# PSU.net
KiCad netlist of a schematic drawn in Altium Designer
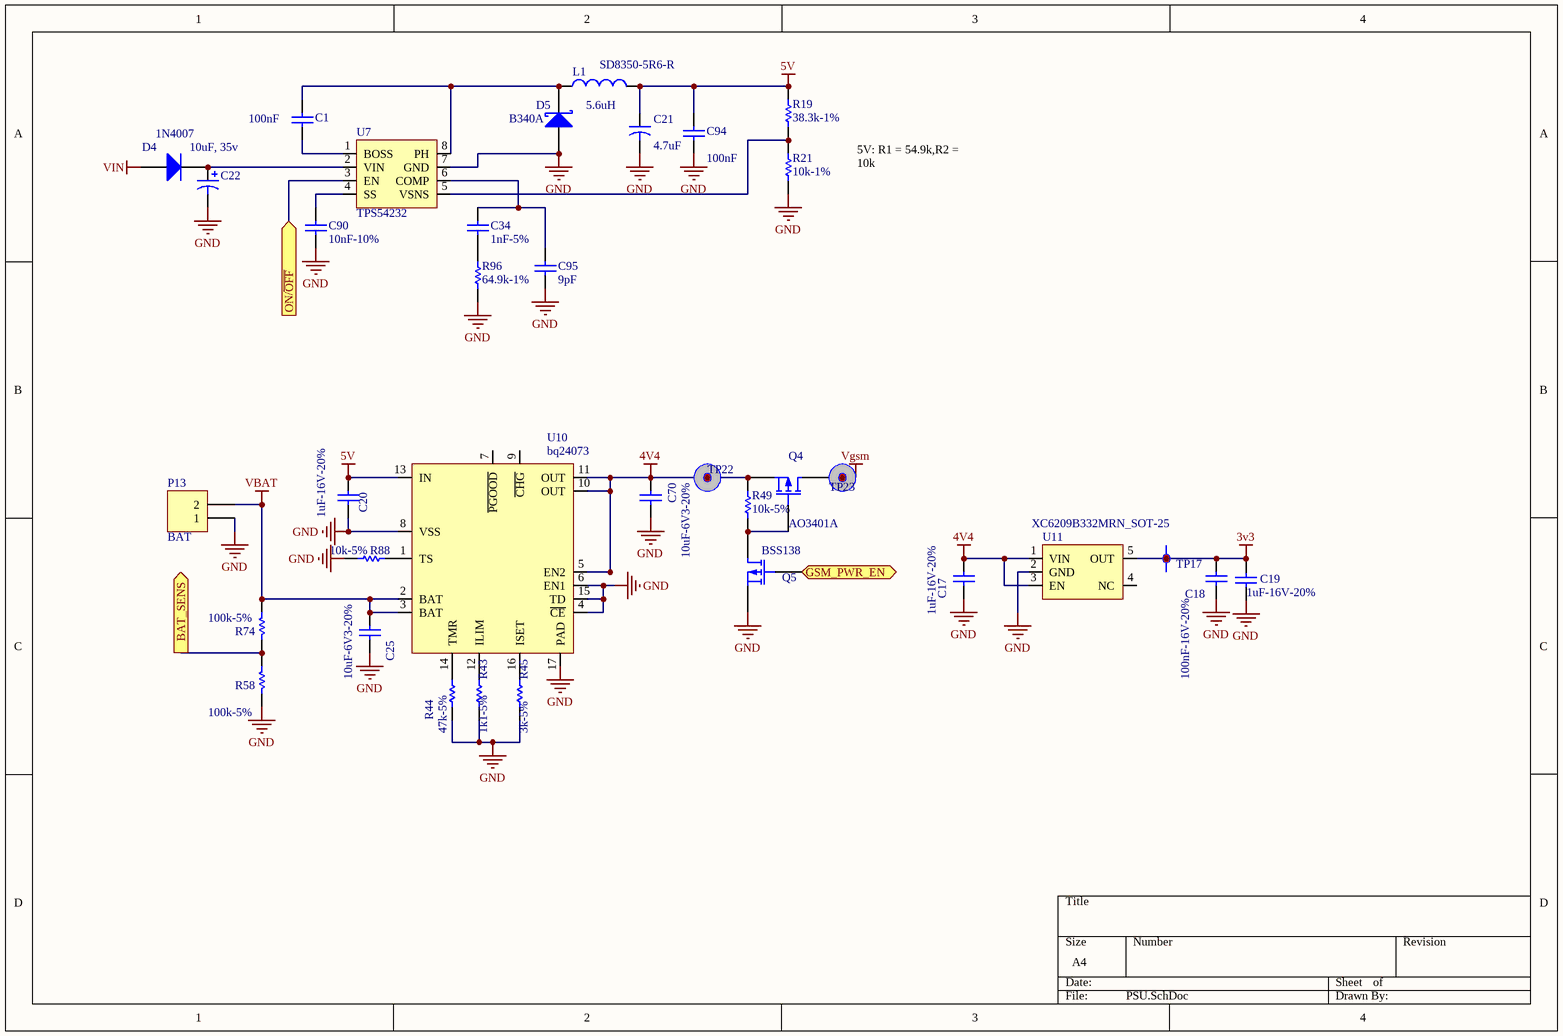
[diagram p0: PSU.SchDoc]

(export (version "E")
  (design (tool "Eeschema 10.0.6"))
  (components
    (comp (ref "C1")
      (value "100nF")
      (footprint "C0402")
      (description "Capacitor")
      (fields (field (name "PUBLISHER") "Altium Limited"))
      (libsource (lib "Miscellaneous Devices") (part "Cap"))
    )
    (comp (ref "C17")
      (value "1uF-16V-20%")
      (footprint "C0603")
      (description "CAP CER 1UF 16V Y5V 0603")
      (fields
        (field (name "MANUFACTURER") "Yageo")
        (field (name "DIGI-KEY PART NUMBER") "311-1372-1-ND")
        (field (name "PUBLISHER") "Altium Limited")
      )
      (libsource (lib "Miscellaneous Devices") (part "Cap"))
    )
    (comp (ref "C18")
      (value "100nF-16V-20%")
      (footprint "C0402")
      (description "CAP CER 0.1UF 16V Y5V 0402")
      (fields
        (field (name "MANUFACTURER") "Yageo")
        (field (name "DIGI-KEY PART NUMBER") "311-1047-1-ND")
        (field (name "PUBLISHER") "Altium Limited")
      )
      (libsource (lib "Miscellaneous Devices") (part "Cap"))
    )
    (comp (ref "C19")
      (value "1uF-16V-20%")
      (footprint "C0603")
      (description "CAP CER 1UF 16V Y5V 0603")
      (fields
        (field (name "MANUFACTURER") "Yageo")
        (field (name "DIGI-KEY PART NUMBER") "311-1372-1-ND")
        (field (name "PUBLISHER") "Altium Limited")
      )
      (libsource (lib "Miscellaneous Devices") (part "Cap"))
    )
    (comp (ref "C20")
      (value "1uF-16V-20%")
      (footprint "C0603")
      (description "CAP CER 1UF 16V Y5V 0603")
      (fields
        (field (name "MANUFACTURER") "Yageo")
        (field (name "DIGI-KEY PART NUMBER") "311-1372-1-ND")
        (field (name "PUBLISHER") "Altium Limited")
      )
      (libsource (lib "Miscellaneous Devices") (part "Cap"))
    )
    (comp (ref "C21")
      (value "4.7uF")
      (footprint "C1206")
      (description "Capacitor")
      (fields (field (name "PUBLISHER") "Altium Limited"))
      (libsource (lib "Miscellaneous Devices") (part "Cap2"))
    )
    (comp (ref "C22")
      (value "10uF, 35v")
      (footprint "CAPACITOR SIZE_C(D5.3)")
      (description "CAP ALUM 10UF 35V 20% SMD")
      (fields
        (field (name "DIGI-KEY PART NUMBER") "PCE3947TR-ND")
        (field (name "MANUFACTURER") "Panasonic Electronic Components")
        (field (name "PUBLISHER") "Altium Limited")
      )
      (libsource (lib "Miscellaneous Devices") (part "Cap Pol3"))
    )
    (comp (ref "C25")
      (value "10uF-6V3-20%")
      (footprint "C0603")
      (description "CAP CER 10UF 6.3V 20% X5R 0603")
      (fields
        (field (name "MANUFACTURER") "Yageo")
        (field (name "DIGI-KEY PART NUMBER") "311-1448-1-ND")
        (field (name "PUBLISHER") "Altium Limited")
      )
      (libsource (lib "Miscellaneous Devices") (part "Cap"))
    )
    (comp (ref "C34")
      (value "1nF-5%")
      (footprint "C0402")
      (description "Non-Polarized Capacitor")
      (fields (field (name "DIGI-KEY PART NUMBER") "311-1122-1-ND") (field (name "MANUFACTURER") "Yageo"))
      (libsource (lib "Capacitor") (part "1nF-50V-C0805"))
    )
    (comp (ref "C70")
      (value "10uF-6V3-20%")
      (footprint "C0603")
      (description "CAP CER 10UF 6.3V 20% X5R 0603")
      (fields
        (field (name "MANUFACTURER") "Yageo")
        (field (name "DIGI-KEY PART NUMBER") "311-1448-1-ND")
        (field (name "PUBLISHER") "Altium Limited")
      )
      (libsource (lib "Miscellaneous Devices") (part "Cap"))
    )
    (comp (ref "C90")
      (value "10nF-10%")
      (footprint "C0402")
      (description "Non-Polarized Capacitor")
      (fields (field (name "DIGI-KEY PART NUMBER") "311-1136-1-ND") (field (name "MANUFACTURER") "Yageo"))
      (libsource (lib "Capacitor") (part "10nF-50V-C0805"))
    )
    (comp (ref "C94")
      (value "100nF")
      (footprint "C0402")
      (description "Capacitor")
      (fields (field (name "PUBLISHER") "Altium Limited"))
      (libsource (lib "Miscellaneous Devices") (part "Cap"))
    )
    (comp (ref "C95")
      (value "9pF")
      (footprint "C0402")
      (description "Non-Polarized Capacitor")
      (fields (field (name "DIGI-KEY PART NUMBER") "311-1098-1-ND") (field (name "MANUFACTURER") "Yageo"))
      (libsource (lib "Capacitor") (part "9pF-50V-C0805"))
    )
    (comp (ref "D4")
      (value "1N4007")
      (footprint "DO-214AC (SMA)")
      (description "DIODE GEN PURPOSE 1000V 1A SMA")
      (fields
        (field (name "DIGI-KEY PART NUMBER") "641-1018-1-ND")
        (field (name "MANUFACTURER PART NUMBER") "CGRA4007-G")
        (field (name "PUBLISHER") "Altium Limited")
      )
      (libsource (lib "Miscellaneous Devices") (part "Diode"))
    )
    (comp (ref "D5")
      (value "B340A")
      (footprint "DO-214AC (SMA)")
      (description "DIODE SCHOTTKY 40V 3A SMA")
      (fields
        (field (name "DIGI-KEY PART NUMBER") "B340A-E3/61TGITR-ND")
        (field (name "MANUFACTURER PART NUMBER") "B340A-E3/61T")
        (field (name "PUBLISHER") "Altium Limited")
      )
      (libsource (lib "Miscellaneous Devices") (part "D Schottky"))
    )
    (comp (ref "L1")
      (value "SD8350-5R6-R")
      (footprint "SD8350-5R6-R")
      (description "Digikey part SD8350-4R7-R")
      (fields (field (name "ALTIUM_VALUE") "5.6uH") (field (name "PUBLISHER") "Altium Limited"))
      (libsource (lib "Miscellaneous Devices") (part "Inductor"))
    )
    (comp (ref "P13")
      (value "BAT")
      (footprint "HDR1X2")
      (description "Header, 2-Pin")
      (fields (field (name "PUBLISHER") "Altium Limited"))
      (libsource (lib "Miscellaneous Connectors") (part "Header 2"))
    )
    (comp (ref "Q4")
      (value "AO3401A")
      (footprint "SOT23-3")
      (description "MOSFET P-CH -30V -4.3A SOT23")
      (fields
        (field (name "DIGI-KEY PART NUMBER") "785-1001-1-ND")
        (field (name "MANUFACTURER") "Alpha & Omega Semiconductor Inc")
        (field (name "PUBLISHER") "Altium Limited")
      )
      (libsource (lib "Miscellaneous Devices") (part "MOSFET-P"))
    )
    (comp (ref "Q5")
      (value "BSS138")
      (footprint "SOT23-3")
      (description "MOSFET N-CH 50V 200MA SOT23-3")
      (fields
        (field (name "DIGI-KEY PART NUMBER") "BSS138-FDICT-ND")
        (field (name "MANUFACTURER") "Diodes Inc")
        (field (name "PUBLISHER") "Altium Limited")
      )
      (libsource (lib "") (part "MOSFET-P_1"))
    )
    (comp (ref "R19")
      (value "38.3k-1%")
      (footprint "R0402")
      (description "RES 38.3k OHM 1/4W 1% 0805 SMD")
      (fields (field (name "DIGI-KEY PART NUMBER") "311-38.3KCRTR-ND") (field (name "MANUFACTURER") "Yageo"))
      (libsource (lib "All_Resistor") (part "38.3k-1%-R0805"))
    )
    (comp (ref "R21")
      (value "10k-1%")
      (footprint "R0402")
      (description "RES 10k OHM 1/4W 1% 0805 SMD")
      (fields (field (name "DIGI-KEY PART NUMBER") "311-10.0KCRTR-ND") (field (name "MANUFACTURER") "Yageo"))
      (libsource (lib "All_Resistor") (part "10k-1%-R0805"))
    )
    (comp (ref "R43")
      (value "1k1-5%")
      (footprint "R0402")
      (description "RES 1.1K OHM 1/16W 5% 0402 SMD")
      (fields
        (field (name "DIGI-KEY PART NUMBER") "311-1.1KJRCT-ND")
        (field (name "MANUFACTURER") "Yageo")
        (field (name "PUBLISHER") "Altium Limited")
      )
      (libsource (lib "Miscellaneous Devices") (part "Res1"))
    )
    (comp (ref "R44")
      (value "47k-5%")
      (footprint "R0402")
      (description "RES 47K OHM 1/16W 5% 0402 SMD")
      (fields
        (field (name "DIGI-KEY PART NUMBER") "311-47KJRCT-ND")
        (field (name "MANUFACTURER") "Yageo")
        (field (name "PUBLISHER") "Altium Limited")
      )
      (libsource (lib "Miscellaneous Devices") (part "Res1"))
    )
    (comp (ref "R45")
      (value "3k-5%")
      (footprint "R0402")
      (description "RES 1.5K OHM 1/16W 5% 0402 SMD")
      (fields
        (field (name "DIGI-KEY PART NUMBER") "311-3.0KJRCT-ND")
        (field (name "MANUFACTURER") "Yageo")
        (field (name "PUBLISHER") "Altium Limited")
      )
      (libsource (lib "Miscellaneous Devices") (part "Res1"))
    )
    (comp (ref "R49")
      (value "10k-5%")
      (footprint "R0402")
      (description "RES 10K OHM 1/16W 5% 0402 SMD")
      (fields
        (field (name "DIGI-KEY PART NUMBER") "311-10KJRCT-ND")
        (field (name "MANUFACTURER") "Yageo")
        (field (name "PUBLISHER") "Altium Limited")
      )
      (libsource (lib "Miscellaneous Devices") (part "Res1"))
    )
    (comp (ref "R58")
      (value "100k-5%")
      (footprint "R0402")
      (description "RES 100K OHM 1/16W 5% 0402 SMD")
      (fields
        (field (name "DIGI-KEY PART NUMBER") "311-100KJRCT-ND")
        (field (name "MANUFACTURER") "Yageo")
        (field (name "PUBLISHER") "Altium Limited")
      )
      (libsource (lib "Miscellaneous Devices") (part "Res1"))
    )
    (comp (ref "R74")
      (value "100k-5%")
      (footprint "R0402")
      (description "RES 100K OHM 1/16W 5% 0402 SMD")
      (fields
        (field (name "DIGI-KEY PART NUMBER") "311-100KJRCT-ND")
        (field (name "MANUFACTURER") "Yageo")
        (field (name "PUBLISHER") "Altium Limited")
      )
      (libsource (lib "Miscellaneous Devices") (part "Res1"))
    )
    (comp (ref "R88")
      (value "10k-5%")
      (footprint "R0402")
      (description "RES 10K OHM 1/16W 5% 0402 SMD")
      (fields
        (field (name "DIGI-KEY PART NUMBER") "311-10KJRCT-ND")
        (field (name "MANUFACTURER") "Yageo")
        (field (name "PUBLISHER") "Altium Limited")
      )
      (libsource (lib "Miscellaneous Devices") (part "Res1"))
    )
    (comp (ref "R96")
      (value "64.9k-1%")
      (footprint "R0402")
      (description "RES 64.9k OHM 1/4W 1% 0805 SMD")
      (fields (field (name "DIGI-KEY PART NUMBER") "311-64.9KCRTR-ND") (field (name "MANUFACTURER") "Yageo"))
      (libsource (lib "All_Resistor") (part "64.9k-1%-R0805"))
    )
    (comp (ref "TP17") (value "TP") (footprint "test_point") (libsource (lib "") (part "TP_1")))
    (comp (ref "TP22") (value "TP") (footprint "test_point") (libsource (lib "Lib") (part "TP")))
    (comp (ref "TP23") (value "TP") (footprint "test_point") (libsource (lib "Lib") (part "TP")))
    (comp (ref "U7")
      (value "TPS54232")
      (footprint "SOIC127P600-8AL")
      (libsource (lib "TPS54232") (part "Component_1"))
    )
    (comp (ref "U10")
      (value "bq24073")
      (footprint "pq24073")
      (description "IC LI-ION CHARGE/PWR MGMT 16-QFN")
      (fields
        (field (name "DIGI-KEY PART NUMBER") "296-23839-1-ND")
        (field (name "MANUFACTURER") "Texas Instruments")
      )
      (libsource (lib "TI_Power") (part "BATTERY_CHARGER"))
    )
    (comp (ref "U11")
      (value "XC6209B332MRN_SOT-25")
      (footprint "SOT23-5")
      (fields (field (name "MANUFACTURER") "Tyrone"))
      (libsource (lib "Schlib1") (part "XC6209B332MRN_SOT-25"))
    )
  )
  (nets
    (net (code "1") (name "/BAT_SENS") (class "Default")
      (node (ref "R58") (pin "2") (pinfunction "2_2") (pintype "passive"))
      (node (ref "R74") (pin "1") (pinfunction "1_1") (pintype "passive"))
    )
    (net (code "2") (name "/GSM_PWR_EN") (class "Default")
      (node (ref "Q5") (pin "1") (pinfunction "G_1") (pintype "passive"))
    )
    (net (code "3") (name "/ON{slash}~{OFF}") (class "Default")
      (node (ref "U7") (pin "3") (pinfunction "EN_3") (pintype "passive"))
    )
    (net (code "4") (name "3v3") (class "Default")
      (node (ref "C18") (pin "2") (pinfunction "2_2") (pintype "passive"))
      (node (ref "C19") (pin "1") (pinfunction "1_1") (pintype "passive"))
      (node (ref "TP17") (pin "1") (pinfunction "TP_1") (pintype "passive"))
      (node (ref "U11") (pin "5") (pinfunction "OUT_5") (pintype "passive"))
    )
    (net (code "5") (name "4V4") (class "Default")
      (node (ref "C17") (pin "1") (pinfunction "1_1") (pintype "passive"))
      (node (ref "C70") (pin "2") (pinfunction "2_2") (pintype "passive"))
      (node (ref "Q4") (pin "2") (pinfunction "S_2") (pintype "passive"))
      (node (ref "R49") (pin "1") (pinfunction "1_1") (pintype "passive"))
      (node (ref "TP22") (pin "1") (pinfunction "TP_1") (pintype "passive"))
      (node (ref "U10") (pin "10") (pinfunction "OUT_10") (pintype "passive"))
      (node (ref "U10") (pin "11") (pinfunction "OUT_11") (pintype "passive"))
      (node (ref "U10") (pin "5") (pinfunction "EN2_5") (pintype "passive"))
      (node (ref "U11") (pin "1") (pinfunction "VIN_1") (pintype "passive"))
      (node (ref "U11") (pin "3") (pinfunction "EN_3") (pintype "passive"))
    )
    (net (code "6") (name "5V") (class "Default")
      (node (ref "C20") (pin "2") (pinfunction "2_2") (pintype "passive"))
      (node (ref "C21") (pin "1") (pinfunction "1_1") (pintype "passive"))
      (node (ref "C94") (pin "2") (pinfunction "2_2") (pintype "passive"))
      (node (ref "L1") (pin "2") (pinfunction "2_2") (pintype "passive"))
      (node (ref "R19") (pin "2") (pinfunction "2_2") (pintype "passive"))
      (node (ref "U10") (pin "13") (pinfunction "IN_13") (pintype "passive"))
    )
    (net (code "7") (name "GND") (class "Default")
      (node (ref "C17") (pin "2") (pinfunction "2_2") (pintype "passive"))
      (node (ref "C18") (pin "1") (pinfunction "1_1") (pintype "passive"))
      (node (ref "C19") (pin "2") (pinfunction "2_2") (pintype "passive"))
      (node (ref "C20") (pin "1") (pinfunction "1_1") (pintype "passive"))
      (node (ref "C21") (pin "2") (pinfunction "2_2") (pintype "passive"))
      (node (ref "C22") (pin "2") (pinfunction "2_2") (pintype "passive"))
      (node (ref "C25") (pin "1") (pinfunction "1_1") (pintype "passive"))
      (node (ref "C70") (pin "1") (pinfunction "1_1") (pintype "passive"))
      (node (ref "C90") (pin "1") (pinfunction "1_1") (pintype "passive"))
      (node (ref "C94") (pin "1") (pinfunction "1_1") (pintype "passive"))
      (node (ref "C95") (pin "1") (pinfunction "1_1") (pintype "passive"))
      (node (ref "D5") (pin "1") (pinfunction "A_1") (pintype "passive"))
      (node (ref "P13") (pin "1") (pinfunction "1_1") (pintype "passive"))
      (node (ref "Q5") (pin "2") (pinfunction "S_2") (pintype "passive"))
      (node (ref "R21") (pin "1") (pinfunction "1_1") (pintype "passive"))
      (node (ref "R43") (pin "2") (pinfunction "2_2") (pintype "passive"))
      (node (ref "R44") (pin "2") (pinfunction "2_2") (pintype "passive"))
      (node (ref "R45") (pin "2") (pinfunction "2_2") (pintype "passive"))
      (node (ref "R58") (pin "1") (pinfunction "1_1") (pintype "passive"))
      (node (ref "R88") (pin "2") (pinfunction "2_2") (pintype "passive"))
      (node (ref "R96") (pin "1") (pinfunction "1_1") (pintype "passive"))
      (node (ref "U10") (pin "15") (pinfunction "TD_15") (pintype "passive"))
      (node (ref "U10") (pin "17") (pinfunction "PAD_17") (pintype "passive"))
      (node (ref "U10") (pin "4") (pinfunction "~{CE}_4") (pintype "passive"))
      (node (ref "U10") (pin "6") (pinfunction "EN1_6") (pintype "passive"))
      (node (ref "U10") (pin "8") (pinfunction "VSS_8") (pintype "passive"))
      (node (ref "U11") (pin "2") (pinfunction "GND_2") (pintype "passive"))
      (node (ref "U7") (pin "7") (pinfunction "GND_7") (pintype "passive"))
    )
    (net (code "8") (name "Net-(C34-Pad1)") (class "Default")
      (node (ref "C34") (pin "1") (pinfunction "1_1") (pintype "passive"))
      (node (ref "R96") (pin "2") (pinfunction "2_2") (pintype "passive"))
    )
    (net (code "9") (name "Net-(D4-K)") (class "Default")
      (node (ref "C22") (pin "1") (pinfunction "1_1") (pintype "passive"))
      (node (ref "D4") (pin "2") (pinfunction "K_2") (pintype "passive"))
      (node (ref "U7") (pin "2") (pinfunction "VIN_2") (pintype "passive"))
    )
    (net (code "10") (name "Net-(D5-K)") (class "Default")
      (node (ref "C1") (pin "1") (pinfunction "1_1") (pintype "passive"))
      (node (ref "D5") (pin "2") (pinfunction "K_2") (pintype "passive"))
      (node (ref "L1") (pin "1") (pinfunction "1_1") (pintype "passive"))
      (node (ref "U7") (pin "8") (pinfunction "PH_8") (pintype "passive"))
    )
    (net (code "11") (name "Net-(Q4-G)") (class "Default")
      (node (ref "Q4") (pin "1") (pinfunction "G_1") (pintype "passive"))
      (node (ref "Q5") (pin "3") (pinfunction "D_3") (pintype "passive"))
      (node (ref "R49") (pin "2") (pinfunction "2_2") (pintype "passive"))
    )
    (net (code "12") (name "Net-(U7-BOSS)") (class "Default")
      (node (ref "C1") (pin "2") (pinfunction "2_2") (pintype "passive"))
      (node (ref "U7") (pin "1") (pinfunction "BOSS_1") (pintype "passive"))
    )
    (net (code "13") (name "Net-(U7-COMP)") (class "Default")
      (node (ref "C34") (pin "2") (pinfunction "2_2") (pintype "passive"))
      (node (ref "C95") (pin "2") (pinfunction "2_2") (pintype "passive"))
      (node (ref "U7") (pin "6") (pinfunction "COMP_6") (pintype "passive"))
    )
    (net (code "14") (name "Net-(U7-SS)") (class "Default")
      (node (ref "C90") (pin "2") (pinfunction "2_2") (pintype "passive"))
      (node (ref "U7") (pin "4") (pinfunction "SS_4") (pintype "passive"))
    )
    (net (code "15") (name "Net-(U7-VSNS)") (class "Default")
      (node (ref "R19") (pin "1") (pinfunction "1_1") (pintype "passive"))
      (node (ref "R21") (pin "2") (pinfunction "2_2") (pintype "passive"))
      (node (ref "U7") (pin "5") (pinfunction "VSNS_5") (pintype "passive"))
    )
    (net (code "16") (name "Net-(U10-ILIM)") (class "Default")
      (node (ref "R43") (pin "1") (pinfunction "1_1") (pintype "passive"))
      (node (ref "U10") (pin "12") (pinfunction "ILIM_12") (pintype "passive"))
    )
    (net (code "17") (name "Net-(U10-ISET)") (class "Default")
      (node (ref "R45") (pin "1") (pinfunction "1_1") (pintype "passive"))
      (node (ref "U10") (pin "16") (pinfunction "ISET_16") (pintype "passive"))
    )
    (net (code "18") (name "Net-(U10-TMR)") (class "Default")
      (node (ref "R44") (pin "1") (pinfunction "1_1") (pintype "passive"))
      (node (ref "U10") (pin "14") (pinfunction "TMR_14") (pintype "passive"))
    )
    (net (code "19") (name "Net-(U10-TS)") (class "Default")
      (node (ref "R88") (pin "1") (pinfunction "1_1") (pintype "passive"))
      (node (ref "U10") (pin "1") (pinfunction "TS_1") (pintype "passive"))
    )
    (net (code "20") (name "VBAT") (class "Default")
      (node (ref "C25") (pin "2") (pinfunction "2_2") (pintype "passive"))
      (node (ref "P13") (pin "2") (pinfunction "2_2") (pintype "passive"))
      (node (ref "R74") (pin "2") (pinfunction "2_2") (pintype "passive"))
      (node (ref "U10") (pin "2") (pinfunction "BAT_2") (pintype "passive"))
      (node (ref "U10") (pin "3") (pinfunction "BAT_3") (pintype "passive"))
    )
    (net (code "21") (name "VIN") (class "Default")
      (node (ref "D4") (pin "1") (pinfunction "A_1") (pintype "passive"))
    )
    (net (code "22") (name "Vgsm") (class "Default")
      (node (ref "Q4") (pin "3") (pinfunction "D_3") (pintype "passive"))
      (node (ref "TP23") (pin "1") (pinfunction "TP_1") (pintype "passive"))
    )
    (net (code "23") (name "unconnected-(U10-~{CHG}-Pad9)") (class "Default")
      (node (ref "U10") (pin "9") (pinfunction "~{CHG}_9") (pintype "passive"))
    )
    (net (code "24") (name "unconnected-(U10-~{PGOOD}-Pad7)") (class "Default")
      (node (ref "U10") (pin "7") (pinfunction "~{PGOOD}_7") (pintype "passive"))
    )
    (net (code "25") (name "unconnected-(U11-NC-Pad4)") (class "Default")
      (node (ref "U11") (pin "4") (pinfunction "NC_4") (pintype "passive"))
    )
  )
)
